# Tray3.net
KiCad netlist of a schematic drawn in Altium Designer
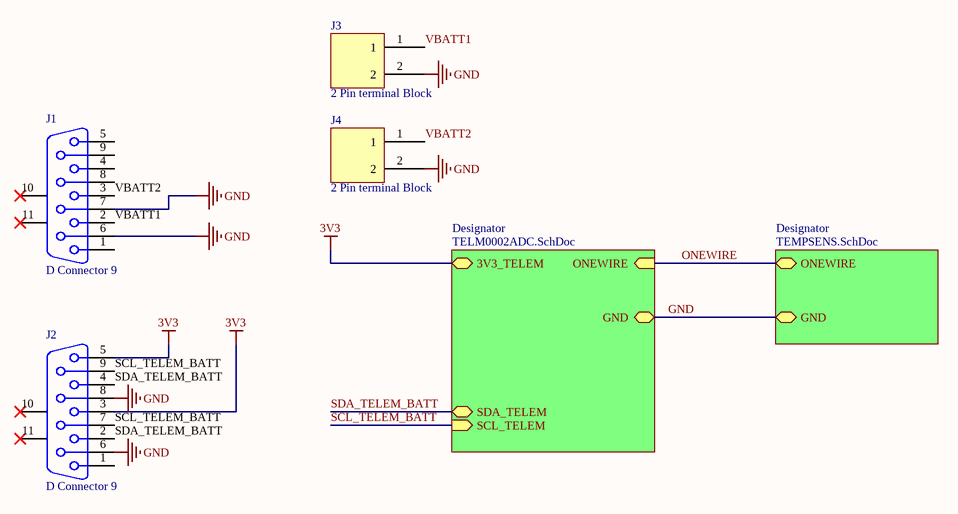
[diagram p0: Tray3.SchDoc]

(export (version "E")
  (design (tool "Eeschema 10.0.6"))
  (components
    (comp (ref "J1")
      (value "D Connector 9")
      (footprint "DSUB Upright")
      (description "Receptacle Assembly, 9 Position, Right Angle")
      (libsource (lib "Tray 3 V2.0") (part "D Connector 9"))
    )
    (comp (ref "J2")
      (value "D Connector 9")
      (footprint "DSUB Upright")
      (description "Receptacle Assembly, 9 Position, Right Angle")
      (libsource (lib "Tray 3 V2.0") (part "D Connector 9"))
    )
    (comp (ref "J3")
      (value "2 Pin terminal Block")
      (footprint "5.05mm Terminal Block - 2")
      (description "Terminal Block, 5.08mm")
      (libsource (lib "Tray 3 V2.0") (part "2 Terminal Block"))
    )
    (comp (ref "J4")
      (value "2 Pin terminal Block")
      (footprint "5.05mm Terminal Block - 2")
      (description "Terminal Block, 5.08mm")
      (libsource (lib "Tray 3 V2.0") (part "2 Terminal Block"))
    )
  )
  (nets
    (net (code "2") (name "/SCL_TELEM_BATT") (class "Default")
      (node (ref "J2") (pin "7") (pinfunction "7_7") (pintype "passive"))
      (node (ref "J2") (pin "9") (pinfunction "9_9") (pintype "passive"))
    )
    (net (code "3") (name "/SDA_TELEM_BATT") (class "Default")
      (node (ref "J2") (pin "2") (pinfunction "2_2") (pintype "passive"))
      (node (ref "J2") (pin "4") (pinfunction "4_4") (pintype "passive"))
    )
    (net (code "4") (name "/VBATT1") (class "Default")
      (node (ref "J1") (pin "2") (pinfunction "2_2") (pintype "passive"))
      (node (ref "J3") (pin "1") (pinfunction "1_1") (pintype "passive"))
    )
    (net (code "5") (name "/VBATT2") (class "Default")
      (node (ref "J1") (pin "3") (pinfunction "3_3") (pintype "passive"))
      (node (ref "J4") (pin "1") (pinfunction "1_1") (pintype "passive"))
    )
    (net (code "6") (name "3V3") (class "Default")
      (node (ref "J2") (pin "3") (pinfunction "3_3") (pintype "passive"))
      (node (ref "J2") (pin "5") (pinfunction "5_5") (pintype "passive"))
    )
    (net (code "7") (name "GND") (class "Default")
      (node (ref "J1") (pin "6") (pinfunction "6_6") (pintype "passive"))
      (node (ref "J1") (pin "7") (pinfunction "7_7") (pintype "passive"))
      (node (ref "J2") (pin "6") (pinfunction "6_6") (pintype "passive"))
      (node (ref "J2") (pin "8") (pinfunction "8_8") (pintype "passive"))
      (node (ref "J3") (pin "2") (pinfunction "2_2") (pintype "passive"))
      (node (ref "J4") (pin "2") (pinfunction "2_2") (pintype "passive"))
    )
    (net (code "8") (name "unconnected-(J1-MH1-Pad10)") (class "Default")
      (node (ref "J1") (pin "10") (pinfunction "MH1_10") (pintype "passive+no_connect"))
    )
    (net (code "9") (name "unconnected-(J1-MH2-Pad11)") (class "Default")
      (node (ref "J1") (pin "11") (pinfunction "MH2_11") (pintype "passive+no_connect"))
    )
    (net (code "10") (name "unconnected-(J1-Pad1)") (class "Default")
      (node (ref "J1") (pin "1") (pinfunction "1_1") (pintype "passive"))
    )
    (net (code "11") (name "unconnected-(J1-Pad4)") (class "Default")
      (node (ref "J1") (pin "4") (pinfunction "4_4") (pintype "passive"))
    )
    (net (code "12") (name "unconnected-(J1-Pad5)") (class "Default")
      (node (ref "J1") (pin "5") (pinfunction "5_5") (pintype "passive"))
    )
    (net (code "13") (name "unconnected-(J1-Pad8)") (class "Default")
      (node (ref "J1") (pin "8") (pinfunction "8_8") (pintype "passive"))
    )
    (net (code "14") (name "unconnected-(J1-Pad9)") (class "Default")
      (node (ref "J1") (pin "9") (pinfunction "9_9") (pintype "passive"))
    )
    (net (code "15") (name "unconnected-(J2-MH1-Pad10)") (class "Default")
      (node (ref "J2") (pin "10") (pinfunction "MH1_10") (pintype "passive+no_connect"))
    )
    (net (code "16") (name "unconnected-(J2-MH2-Pad11)") (class "Default")
      (node (ref "J2") (pin "11") (pinfunction "MH2_11") (pintype "passive+no_connect"))
    )
    (net (code "17") (name "unconnected-(J2-Pad1)") (class "Default")
      (node (ref "J2") (pin "1") (pinfunction "1_1") (pintype "passive"))
    )
  )
)
